# CIRCLE.net
KiCad netlist of a schematic drawn in EAGLE
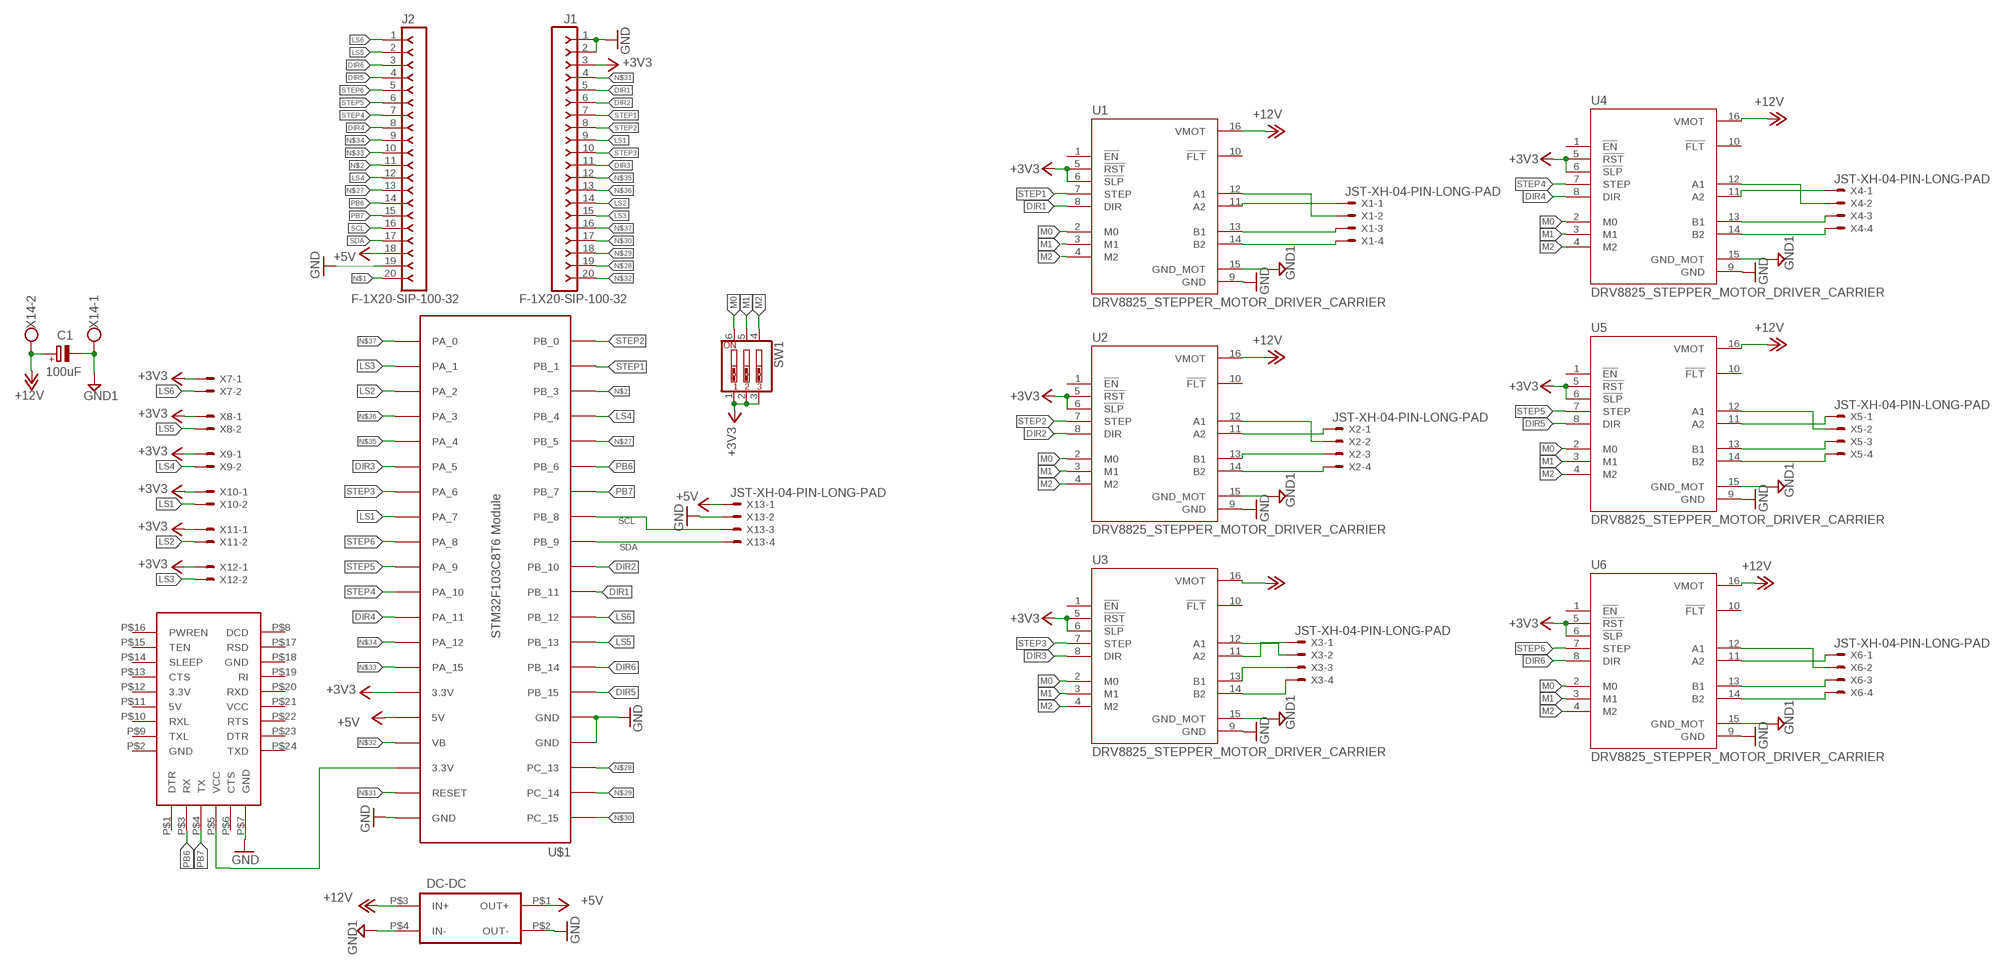
[diagram p0: schematic, sheet 1]

(export (version "E")
  (design (tool "Eeschema 10.0.6"))
  (components
    (comp (ref "C1")
      (value "100uF")
      (footprint "eagle-import:E3,5-8")
      (libsource (lib "eagle-import") (part "CPOL-EUE3.5-8"))
    )
    (comp (ref "J1")
      (value "F-1X20-SIP-100-32")
      (footprint "eagle-import:SIP-100-20-32")
      (libsource (lib "eagle-import") (part "F-1X20-SIP-100-32"))
    )
    (comp (ref "J2")
      (value "F-1X20-SIP-100-32")
      (footprint "eagle-import:SIP-100-20-32")
      (libsource (lib "eagle-import") (part "F-1X20-SIP-100-32"))
    )
    (comp (ref "SW1")
      (value "SW_DIP-3")
      (footprint "eagle-import:EDG-03")
      (libsource (lib "eagle-import") (part "SW_DIP-3"))
    )
    (comp (ref "U$1")
      (value "STM32F103C8T6-MODULE")
      (footprint "eagle-import:STM32F103C8T6-MODULE")
      (libsource (lib "eagle-import") (part "STM32F103C8T6-MODULE"))
    )
    (comp (ref "U$2")
      (value "DC-DC_CONV")
      (footprint "eagle-import:DC-DC_CONV")
      (libsource (lib "eagle-import") (part "DC-DC_CONV"))
    )
    (comp (ref "U$3")
      (value "FT232RL_FTDI")
      (footprint "eagle-import:FT232RL_FTDI")
      (libsource (lib "eagle-import") (part "FT232RL_FTDI"))
    )
    (comp (ref "U1")
      (value "DRV8825_STEPPER_MOTOR_DRIVER_CARRIER")
      (footprint "eagle-import:IC_DRV8825_STEPPER_MOTOR_DRIVER_CARRIER")
      (fields (field (name "MF") "Pololu") (field (name "MP") "DRV8825 STEPPER MOTOR DRIVER CARRIER"))
      (libsource (lib "eagle-import") (part "DRV8825_STEPPER_MOTOR_DRIVER_CARRIER"))
    )
    (comp (ref "U2")
      (value "DRV8825_STEPPER_MOTOR_DRIVER_CARRIER")
      (footprint "eagle-import:IC_DRV8825_STEPPER_MOTOR_DRIVER_CARRIER")
      (fields (field (name "MF") "Pololu") (field (name "MP") "DRV8825 STEPPER MOTOR DRIVER CARRIER"))
      (libsource (lib "eagle-import") (part "DRV8825_STEPPER_MOTOR_DRIVER_CARRIER"))
    )
    (comp (ref "U3")
      (value "DRV8825_STEPPER_MOTOR_DRIVER_CARRIER")
      (footprint "eagle-import:IC_DRV8825_STEPPER_MOTOR_DRIVER_CARRIER")
      (fields (field (name "MF") "Pololu") (field (name "MP") "DRV8825 STEPPER MOTOR DRIVER CARRIER"))
      (libsource (lib "eagle-import") (part "DRV8825_STEPPER_MOTOR_DRIVER_CARRIER"))
    )
    (comp (ref "U4")
      (value "DRV8825_STEPPER_MOTOR_DRIVER_CARRIER")
      (footprint "eagle-import:IC_DRV8825_STEPPER_MOTOR_DRIVER_CARRIER")
      (fields (field (name "MF") "Pololu") (field (name "MP") "DRV8825 STEPPER MOTOR DRIVER CARRIER"))
      (libsource (lib "eagle-import") (part "DRV8825_STEPPER_MOTOR_DRIVER_CARRIER"))
    )
    (comp (ref "U5")
      (value "DRV8825_STEPPER_MOTOR_DRIVER_CARRIER")
      (footprint "eagle-import:IC_DRV8825_STEPPER_MOTOR_DRIVER_CARRIER")
      (fields (field (name "MF") "Pololu") (field (name "MP") "DRV8825 STEPPER MOTOR DRIVER CARRIER"))
      (libsource (lib "eagle-import") (part "DRV8825_STEPPER_MOTOR_DRIVER_CARRIER"))
    )
    (comp (ref "U6")
      (value "DRV8825_STEPPER_MOTOR_DRIVER_CARRIER")
      (footprint "eagle-import:IC_DRV8825_STEPPER_MOTOR_DRIVER_CARRIER")
      (fields (field (name "MF") "Pololu") (field (name "MP") "DRV8825 STEPPER MOTOR DRIVER CARRIER"))
      (libsource (lib "eagle-import") (part "DRV8825_STEPPER_MOTOR_DRIVER_CARRIER"))
    )
    (comp (ref "X1")
      (value "JST-XH-04-PIN-LONG-PAD")
      (footprint "eagle-import:JST-XH-04-PACKAGE-LONG-PAD")
      (libsource (lib "eagle-import") (part "JST-XH-04-PIN-LONG-PAD"))
    )
    (comp (ref "X2")
      (value "JST-XH-04-PIN-LONG-PAD")
      (footprint "eagle-import:JST-XH-04-PACKAGE-LONG-PAD")
      (libsource (lib "eagle-import") (part "JST-XH-04-PIN-LONG-PAD"))
    )
    (comp (ref "X3")
      (value "JST-XH-04-PIN-LONG-PAD")
      (footprint "eagle-import:JST-XH-04-PACKAGE-LONG-PAD")
      (libsource (lib "eagle-import") (part "JST-XH-04-PIN-LONG-PAD"))
    )
    (comp (ref "X4")
      (value "JST-XH-04-PIN-LONG-PAD")
      (footprint "eagle-import:JST-XH-04-PACKAGE-LONG-PAD")
      (libsource (lib "eagle-import") (part "JST-XH-04-PIN-LONG-PAD"))
    )
    (comp (ref "X5")
      (value "JST-XH-04-PIN-LONG-PAD")
      (footprint "eagle-import:JST-XH-04-PACKAGE-LONG-PAD")
      (libsource (lib "eagle-import") (part "JST-XH-04-PIN-LONG-PAD"))
    )
    (comp (ref "X6")
      (value "JST-XH-04-PIN-LONG-PAD")
      (footprint "eagle-import:JST-XH-04-PACKAGE-LONG-PAD")
      (libsource (lib "eagle-import") (part "JST-XH-04-PIN-LONG-PAD"))
    )
    (comp (ref "X7")
      (value "JST-XH-02-PIN-LONG-PAD")
      (footprint "eagle-import:JST-XH-02-PACKAGE-LONG-PAD")
      (libsource (lib "eagle-import") (part "JST-XH-02-PIN-LONG-PAD"))
    )
    (comp (ref "X8")
      (value "JST-XH-02-PIN-LONG-PAD")
      (footprint "eagle-import:JST-XH-02-PACKAGE-LONG-PAD")
      (libsource (lib "eagle-import") (part "JST-XH-02-PIN-LONG-PAD"))
    )
    (comp (ref "X9")
      (value "JST-XH-02-PIN-LONG-PAD")
      (footprint "eagle-import:JST-XH-02-PACKAGE-LONG-PAD")
      (libsource (lib "eagle-import") (part "JST-XH-02-PIN-LONG-PAD"))
    )
    (comp (ref "X10")
      (value "JST-XH-02-PIN-LONG-PAD")
      (footprint "eagle-import:JST-XH-02-PACKAGE-LONG-PAD")
      (libsource (lib "eagle-import") (part "JST-XH-02-PIN-LONG-PAD"))
    )
    (comp (ref "X11")
      (value "JST-XH-02-PIN-LONG-PAD")
      (footprint "eagle-import:JST-XH-02-PACKAGE-LONG-PAD")
      (libsource (lib "eagle-import") (part "JST-XH-02-PIN-LONG-PAD"))
    )
    (comp (ref "X12")
      (value "JST-XH-02-PIN-LONG-PAD")
      (footprint "eagle-import:JST-XH-02-PACKAGE-LONG-PAD")
      (libsource (lib "eagle-import") (part "JST-XH-02-PIN-LONG-PAD"))
    )
    (comp (ref "X13")
      (value "JST-XH-04-PIN-LONG-PAD")
      (footprint "eagle-import:JST-XH-04-PACKAGE-LONG-PAD")
      (libsource (lib "eagle-import") (part "JST-XH-04-PIN-LONG-PAD"))
    )
    (comp (ref "X14")
      (value "W237-102")
      (footprint "eagle-import:W237-102")
      (fields (field (name "MPN") "237-102"))
      (libsource (lib "eagle-import") (part "W237-102"))
    )
  )
  (nets
    (net (code "1") (name "+3V3") (class "Default")
      (node (ref "J1") (pin "3") (pinfunction "3_3") (pintype "passive"))
      (node (ref "SW1") (pin "1") (pinfunction "1_1") (pintype "passive"))
      (node (ref "SW1") (pin "2") (pinfunction "2_2") (pintype "passive"))
      (node (ref "SW1") (pin "3") (pinfunction "3_3") (pintype "passive"))
      (node (ref "U$1") (pin "3.3V@2") (pinfunction "3.3V_3.3V@2") (pintype "bidirectional"))
      (node (ref "U1") (pin "5") (pinfunction "~{RST}_5") (pintype "input"))
      (node (ref "U1") (pin "6") (pinfunction "~{SLP}_6") (pintype "input"))
      (node (ref "U2") (pin "5") (pinfunction "~{RST}_5") (pintype "input"))
      (node (ref "U2") (pin "6") (pinfunction "~{SLP}_6") (pintype "input"))
      (node (ref "U3") (pin "5") (pinfunction "~{RST}_5") (pintype "input"))
      (node (ref "U3") (pin "6") (pinfunction "~{SLP}_6") (pintype "input"))
      (node (ref "U4") (pin "5") (pinfunction "~{RST}_5") (pintype "input"))
      (node (ref "U4") (pin "6") (pinfunction "~{SLP}_6") (pintype "input"))
      (node (ref "U5") (pin "5") (pinfunction "~{RST}_5") (pintype "input"))
      (node (ref "U5") (pin "6") (pinfunction "~{SLP}_6") (pintype "input"))
      (node (ref "U6") (pin "5") (pinfunction "~{RST}_5") (pintype "input"))
      (node (ref "U6") (pin "6") (pinfunction "~{SLP}_6") (pintype "input"))
      (node (ref "X10") (pin "1") (pinfunction "S_1") (pintype "passive"))
      (node (ref "X11") (pin "1") (pinfunction "S_1") (pintype "passive"))
      (node (ref "X12") (pin "1") (pinfunction "S_1") (pintype "passive"))
      (node (ref "X7") (pin "1") (pinfunction "S_1") (pintype "passive"))
      (node (ref "X8") (pin "1") (pinfunction "S_1") (pintype "passive"))
      (node (ref "X9") (pin "1") (pinfunction "S_1") (pintype "passive"))
    )
    (net (code "2") (name "+5V") (class "Default")
      (node (ref "J2") (pin "18") (pinfunction "18_18") (pintype "passive"))
      (node (ref "U$1") (pin "5V") (pinfunction "5V_5V") (pintype "bidirectional"))
      (node (ref "U$2") (pin "P$1") (pinfunction "OUT+_P$1") (pintype "bidirectional"))
      (node (ref "X13") (pin "1") (pinfunction "S_1") (pintype "passive"))
    )
    (net (code "3") (name "+12V") (class "Default")
      (node (ref "C1") (pin "+") (pinfunction "+_+") (pintype "passive"))
      (node (ref "U$2") (pin "P$3") (pinfunction "IN+_P$3") (pintype "bidirectional"))
      (node (ref "U1") (pin "16") (pinfunction "VMOT_16") (pintype "power_in"))
      (node (ref "U2") (pin "16") (pinfunction "VMOT_16") (pintype "power_in"))
      (node (ref "U3") (pin "16") (pinfunction "VMOT_16") (pintype "power_in"))
      (node (ref "U4") (pin "16") (pinfunction "VMOT_16") (pintype "power_in"))
      (node (ref "U5") (pin "16") (pinfunction "VMOT_16") (pintype "power_in"))
      (node (ref "U6") (pin "16") (pinfunction "VMOT_16") (pintype "power_in"))
      (node (ref "X14") (pin "2") (pinfunction "KL_2") (pintype "passive"))
    )
    (net (code "4") (name "DIR1") (class "Default")
      (node (ref "J1") (pin "5") (pinfunction "5_5") (pintype "passive"))
      (node (ref "U$1") (pin "PB_11") (pinfunction "PB_11_PB_11") (pintype "bidirectional"))
      (node (ref "U1") (pin "8") (pinfunction "DIR_8") (pintype "input"))
    )
    (net (code "5") (name "DIR2") (class "Default")
      (node (ref "J1") (pin "6") (pinfunction "6_6") (pintype "passive"))
      (node (ref "U$1") (pin "PB_10") (pinfunction "PB_10_PB_10") (pintype "bidirectional"))
      (node (ref "U2") (pin "8") (pinfunction "DIR_8") (pintype "input"))
    )
    (net (code "6") (name "DIR3") (class "Default")
      (node (ref "J1") (pin "11") (pinfunction "11_11") (pintype "passive"))
      (node (ref "U$1") (pin "PA_5") (pinfunction "PA_5_PA_5") (pintype "bidirectional"))
      (node (ref "U3") (pin "8") (pinfunction "DIR_8") (pintype "input"))
    )
    (net (code "7") (name "DIR4") (class "Default")
      (node (ref "J2") (pin "8") (pinfunction "8_8") (pintype "passive"))
      (node (ref "U$1") (pin "PA_11") (pinfunction "PA_11_PA_11") (pintype "bidirectional"))
      (node (ref "U4") (pin "8") (pinfunction "DIR_8") (pintype "input"))
    )
    (net (code "8") (name "DIR5") (class "Default")
      (node (ref "J2") (pin "4") (pinfunction "4_4") (pintype "passive"))
      (node (ref "U$1") (pin "PB_15") (pinfunction "PB_15_PB_15") (pintype "bidirectional"))
      (node (ref "U5") (pin "8") (pinfunction "DIR_8") (pintype "input"))
    )
    (net (code "9") (name "DIR6") (class "Default")
      (node (ref "J2") (pin "3") (pinfunction "3_3") (pintype "passive"))
      (node (ref "U$1") (pin "PB_14") (pinfunction "PB_14_PB_14") (pintype "bidirectional"))
      (node (ref "U6") (pin "8") (pinfunction "DIR_8") (pintype "input"))
    )
    (net (code "10") (name "GND") (class "Default")
      (node (ref "J1") (pin "1") (pinfunction "1_1") (pintype "passive"))
      (node (ref "J1") (pin "2") (pinfunction "2_2") (pintype "passive"))
      (node (ref "J2") (pin "19") (pinfunction "19_19") (pintype "passive"))
      (node (ref "U$1") (pin "GND@1") (pinfunction "GND_GND@1") (pintype "bidirectional"))
      (node (ref "U$1") (pin "GND@2") (pinfunction "GND_GND@2") (pintype "bidirectional"))
      (node (ref "U$1") (pin "GND@3") (pinfunction "GND_GND@3") (pintype "bidirectional"))
      (node (ref "U$2") (pin "P$2") (pinfunction "OUT-_P$2") (pintype "bidirectional"))
      (node (ref "U$3") (pin "P$7") (pinfunction "GND_P$7") (pintype "bidirectional"))
      (node (ref "U1") (pin "9") (pinfunction "GND_9") (pintype "power_in"))
      (node (ref "U2") (pin "9") (pinfunction "GND_9") (pintype "power_in"))
      (node (ref "U3") (pin "9") (pinfunction "GND_9") (pintype "power_in"))
      (node (ref "U4") (pin "9") (pinfunction "GND_9") (pintype "power_in"))
      (node (ref "U5") (pin "9") (pinfunction "GND_9") (pintype "power_in"))
      (node (ref "U6") (pin "9") (pinfunction "GND_9") (pintype "power_in"))
      (node (ref "X13") (pin "2") (pinfunction "S_2") (pintype "passive"))
    )
    (net (code "11") (name "GND1") (class "Default")
      (node (ref "C1") (pin "-") (pinfunction "-_-") (pintype "passive"))
      (node (ref "U$2") (pin "P$4") (pinfunction "IN-_P$4") (pintype "bidirectional"))
      (node (ref "U1") (pin "15") (pinfunction "GND_MOT_15") (pintype "power_in"))
      (node (ref "U2") (pin "15") (pinfunction "GND_MOT_15") (pintype "power_in"))
      (node (ref "U3") (pin "15") (pinfunction "GND_MOT_15") (pintype "power_in"))
      (node (ref "U4") (pin "15") (pinfunction "GND_MOT_15") (pintype "power_in"))
      (node (ref "U5") (pin "15") (pinfunction "GND_MOT_15") (pintype "power_in"))
      (node (ref "U6") (pin "15") (pinfunction "GND_MOT_15") (pintype "power_in"))
      (node (ref "X14") (pin "1") (pinfunction "KL_1") (pintype "passive"))
    )
    (net (code "12") (name "LS1") (class "Default")
      (node (ref "J1") (pin "9") (pinfunction "9_9") (pintype "passive"))
      (node (ref "U$1") (pin "PA_7") (pinfunction "PA_7_PA_7") (pintype "bidirectional"))
      (node (ref "X10") (pin "2") (pinfunction "S_2") (pintype "passive"))
    )
    (net (code "13") (name "LS2") (class "Default")
      (node (ref "J1") (pin "14") (pinfunction "14_14") (pintype "passive"))
      (node (ref "U$1") (pin "PA_2") (pinfunction "PA_2_PA_2") (pintype "bidirectional"))
      (node (ref "X11") (pin "2") (pinfunction "S_2") (pintype "passive"))
    )
    (net (code "14") (name "LS3") (class "Default")
      (node (ref "J1") (pin "15") (pinfunction "15_15") (pintype "passive"))
      (node (ref "U$1") (pin "PA_1") (pinfunction "PA_1_PA_1") (pintype "bidirectional"))
      (node (ref "X12") (pin "2") (pinfunction "S_2") (pintype "passive"))
    )
    (net (code "15") (name "LS4") (class "Default")
      (node (ref "J2") (pin "12") (pinfunction "12_12") (pintype "passive"))
      (node (ref "U$1") (pin "PB_4") (pinfunction "PB_4_PB_4") (pintype "bidirectional"))
      (node (ref "X9") (pin "2") (pinfunction "S_2") (pintype "passive"))
    )
    (net (code "16") (name "LS5") (class "Default")
      (node (ref "J2") (pin "2") (pinfunction "2_2") (pintype "passive"))
      (node (ref "U$1") (pin "PB_13") (pinfunction "PB_13_PB_13") (pintype "bidirectional"))
      (node (ref "X8") (pin "2") (pinfunction "S_2") (pintype "passive"))
    )
    (net (code "17") (name "LS6") (class "Default")
      (node (ref "J2") (pin "1") (pinfunction "1_1") (pintype "passive"))
      (node (ref "U$1") (pin "PB_12") (pinfunction "PB_12_PB_12") (pintype "bidirectional"))
      (node (ref "X7") (pin "2") (pinfunction "S_2") (pintype "passive"))
    )
    (net (code "18") (name "M0") (class "Default")
      (node (ref "SW1") (pin "6") (pinfunction "6_6") (pintype "passive"))
      (node (ref "U1") (pin "2") (pinfunction "M0_2") (pintype "input"))
      (node (ref "U2") (pin "2") (pinfunction "M0_2") (pintype "input"))
      (node (ref "U3") (pin "2") (pinfunction "M0_2") (pintype "input"))
      (node (ref "U4") (pin "2") (pinfunction "M0_2") (pintype "input"))
      (node (ref "U5") (pin "2") (pinfunction "M0_2") (pintype "input"))
      (node (ref "U6") (pin "2") (pinfunction "M0_2") (pintype "input"))
    )
    (net (code "19") (name "M1") (class "Default")
      (node (ref "SW1") (pin "5") (pinfunction "5_5") (pintype "passive"))
      (node (ref "U1") (pin "3") (pinfunction "M1_3") (pintype "input"))
      (node (ref "U2") (pin "3") (pinfunction "M1_3") (pintype "input"))
      (node (ref "U3") (pin "3") (pinfunction "M1_3") (pintype "input"))
      (node (ref "U4") (pin "3") (pinfunction "M1_3") (pintype "input"))
      (node (ref "U5") (pin "3") (pinfunction "M1_3") (pintype "input"))
      (node (ref "U6") (pin "3") (pinfunction "M1_3") (pintype "input"))
    )
    (net (code "20") (name "M2") (class "Default")
      (node (ref "SW1") (pin "4") (pinfunction "4_4") (pintype "passive"))
      (node (ref "U1") (pin "4") (pinfunction "M2_4") (pintype "input"))
      (node (ref "U2") (pin "4") (pinfunction "M2_4") (pintype "input"))
      (node (ref "U3") (pin "4") (pinfunction "M2_4") (pintype "input"))
      (node (ref "U4") (pin "4") (pinfunction "M2_4") (pintype "input"))
      (node (ref "U5") (pin "4") (pinfunction "M2_4") (pintype "input"))
      (node (ref "U6") (pin "4") (pinfunction "M2_4") (pintype "input"))
    )
    (net (code "21") (name "N$1") (class "Default")
      (node (ref "J2") (pin "20") (pinfunction "20_20") (pintype "passive"))
      (node (ref "U$1") (pin "3.3V@1") (pinfunction "3.3V_3.3V@1") (pintype "bidirectional"))
      (node (ref "U$3") (pin "P$5") (pinfunction "VCC_P$5") (pintype "bidirectional"))
    )
    (net (code "22") (name "N$2") (class "Default")
      (node (ref "J2") (pin "11") (pinfunction "11_11") (pintype "passive"))
      (node (ref "U$1") (pin "PB_3") (pinfunction "PB_3_PB_3") (pintype "bidirectional"))
    )
    (net (code "23") (name "N$27") (class "Default")
      (node (ref "J2") (pin "13") (pinfunction "13_13") (pintype "passive"))
      (node (ref "U$1") (pin "PB_5") (pinfunction "PB_5_PB_5") (pintype "bidirectional"))
    )
    (net (code "24") (name "N$28") (class "Default")
      (node (ref "J1") (pin "19") (pinfunction "19_19") (pintype "passive"))
      (node (ref "U$1") (pin "PC_13") (pinfunction "PC_13_PC_13") (pintype "bidirectional"))
    )
    (net (code "25") (name "N$29") (class "Default")
      (node (ref "J1") (pin "18") (pinfunction "18_18") (pintype "passive"))
      (node (ref "U$1") (pin "PC_14") (pinfunction "PC_14_PC_14") (pintype "bidirectional"))
    )
    (net (code "26") (name "N$30") (class "Default")
      (node (ref "J1") (pin "17") (pinfunction "17_17") (pintype "passive"))
      (node (ref "U$1") (pin "PC_15") (pinfunction "PC_15_PC_15") (pintype "bidirectional"))
    )
    (net (code "27") (name "N$31") (class "Default")
      (node (ref "J1") (pin "4") (pinfunction "4_4") (pintype "passive"))
      (node (ref "U$1") (pin "RESET") (pinfunction "RESET_RESET") (pintype "bidirectional"))
    )
    (net (code "28") (name "N$32") (class "Default")
      (node (ref "J1") (pin "20") (pinfunction "20_20") (pintype "passive"))
      (node (ref "U$1") (pin "VB") (pinfunction "VB_VB") (pintype "bidirectional"))
    )
    (net (code "29") (name "N$33") (class "Default")
      (node (ref "J2") (pin "10") (pinfunction "10_10") (pintype "passive"))
      (node (ref "U$1") (pin "PA_15") (pinfunction "PA_15_PA_15") (pintype "bidirectional"))
    )
    (net (code "30") (name "N$34") (class "Default")
      (node (ref "J2") (pin "9") (pinfunction "9_9") (pintype "passive"))
      (node (ref "U$1") (pin "PA_12") (pinfunction "PA_12_PA_12") (pintype "bidirectional"))
    )
    (net (code "31") (name "N$35") (class "Default")
      (node (ref "J1") (pin "12") (pinfunction "12_12") (pintype "passive"))
      (node (ref "U$1") (pin "PA_4") (pinfunction "PA_4_PA_4") (pintype "bidirectional"))
    )
    (net (code "32") (name "N$36") (class "Default")
      (node (ref "J1") (pin "13") (pinfunction "13_13") (pintype "passive"))
      (node (ref "U$1") (pin "PA_3") (pinfunction "PA_3_PA_3") (pintype "bidirectional"))
    )
    (net (code "33") (name "N$37") (class "Default")
      (node (ref "J1") (pin "16") (pinfunction "16_16") (pintype "passive"))
      (node (ref "U$1") (pin "PA_0") (pinfunction "PA_0_PA_0") (pintype "bidirectional"))
    )
    (net (code "34") (name "Net-(U1-A1)") (class "Default")
      (node (ref "U1") (pin "12") (pinfunction "A1_12") (pintype "output"))
      (node (ref "X1") (pin "2") (pinfunction "S_2") (pintype "passive"))
    )
    (net (code "35") (name "Net-(U1-A2)") (class "Default")
      (node (ref "U1") (pin "11") (pinfunction "A2_11") (pintype "output"))
      (node (ref "X1") (pin "1") (pinfunction "S_1") (pintype "passive"))
    )
    (net (code "36") (name "Net-(U1-B1)") (class "Default")
      (node (ref "U1") (pin "13") (pinfunction "B1_13") (pintype "output"))
      (node (ref "X1") (pin "3") (pinfunction "S_3") (pintype "passive"))
    )
    (net (code "37") (name "Net-(U1-B2)") (class "Default")
      (node (ref "U1") (pin "14") (pinfunction "B2_14") (pintype "output"))
      (node (ref "X1") (pin "4") (pinfunction "S_4") (pintype "passive"))
    )
    (net (code "38") (name "Net-(U2-A1)") (class "Default")
      (node (ref "U2") (pin "12") (pinfunction "A1_12") (pintype "output"))
      (node (ref "X2") (pin "2") (pinfunction "S_2") (pintype "passive"))
    )
    (net (code "39") (name "Net-(U2-A2)") (class "Default")
      (node (ref "U2") (pin "11") (pinfunction "A2_11") (pintype "output"))
      (node (ref "X2") (pin "1") (pinfunction "S_1") (pintype "passive"))
    )
    (net (code "40") (name "Net-(U2-B1)") (class "Default")
      (node (ref "U2") (pin "13") (pinfunction "B1_13") (pintype "output"))
      (node (ref "X2") (pin "3") (pinfunction "S_3") (pintype "passive"))
    )
    (net (code "41") (name "Net-(U2-B2)") (class "Default")
      (node (ref "U2") (pin "14") (pinfunction "B2_14") (pintype "output"))
      (node (ref "X2") (pin "4") (pinfunction "S_4") (pintype "passive"))
    )
    (net (code "42") (name "Net-(U3-A1)") (class "Default")
      (node (ref "U3") (pin "12") (pinfunction "A1_12") (pintype "output"))
      (node (ref "X3") (pin "2") (pinfunction "S_2") (pintype "passive"))
    )
    (net (code "43") (name "Net-(U3-A2)") (class "Default")
      (node (ref "U3") (pin "11") (pinfunction "A2_11") (pintype "output"))
      (node (ref "X3") (pin "1") (pinfunction "S_1") (pintype "passive"))
    )
    (net (code "44") (name "Net-(U3-B1)") (class "Default")
      (node (ref "U3") (pin "13") (pinfunction "B1_13") (pintype "output"))
      (node (ref "X3") (pin "3") (pinfunction "S_3") (pintype "passive"))
    )
    (net (code "45") (name "Net-(U3-B2)") (class "Default")
      (node (ref "U3") (pin "14") (pinfunction "B2_14") (pintype "output"))
      (node (ref "X3") (pin "4") (pinfunction "S_4") (pintype "passive"))
    )
    (net (code "46") (name "Net-(U4-A1)") (class "Default")
      (node (ref "U4") (pin "12") (pinfunction "A1_12") (pintype "output"))
      (node (ref "X4") (pin "2") (pinfunction "S_2") (pintype "passive"))
    )
    (net (code "47") (name "Net-(U4-A2)") (class "Default")
      (node (ref "U4") (pin "11") (pinfunction "A2_11") (pintype "output"))
      (node (ref "X4") (pin "1") (pinfunction "S_1") (pintype "passive"))
    )
    (net (code "48") (name "Net-(U4-B1)") (class "Default")
      (node (ref "U4") (pin "13") (pinfunction "B1_13") (pintype "output"))
      (node (ref "X4") (pin "3") (pinfunction "S_3") (pintype "passive"))
    )
    (net (code "49") (name "Net-(U4-B2)") (class "Default")
      (node (ref "U4") (pin "14") (pinfunction "B2_14") (pintype "output"))
      (node (ref "X4") (pin "4") (pinfunction "S_4") (pintype "passive"))
    )
    (net (code "50") (name "Net-(U5-A1)") (class "Default")
      (node (ref "U5") (pin "12") (pinfunction "A1_12") (pintype "output"))
      (node (ref "X5") (pin "2") (pinfunction "S_2") (pintype "passive"))
    )
    (net (code "51") (name "Net-(U5-A2)") (class "Default")
      (node (ref "U5") (pin "11") (pinfunction "A2_11") (pintype "output"))
      (node (ref "X5") (pin "1") (pinfunction "S_1") (pintype "passive"))
    )
    (net (code "52") (name "Net-(U5-B1)") (class "Default")
      (node (ref "U5") (pin "13") (pinfunction "B1_13") (pintype "output"))
      (node (ref "X5") (pin "3") (pinfunction "S_3") (pintype "passive"))
    )
    (net (code "53") (name "Net-(U5-B2)") (class "Default")
      (node (ref "U5") (pin "14") (pinfunction "B2_14") (pintype "output"))
      (node (ref "X5") (pin "4") (pinfunction "S_4") (pintype "passive"))
    )
    (net (code "54") (name "Net-(U6-A1)") (class "Default")
      (node (ref "U6") (pin "12") (pinfunction "A1_12") (pintype "output"))
      (node (ref "X6") (pin "2") (pinfunction "S_2") (pintype "passive"))
    )
    (net (code "55") (name "Net-(U6-A2)") (class "Default")
      (node (ref "U6") (pin "11") (pinfunction "A2_11") (pintype "output"))
      (node (ref "X6") (pin "1") (pinfunction "S_1") (pintype "passive"))
    )
    (net (code "56") (name "Net-(U6-B1)") (class "Default")
      (node (ref "U6") (pin "13") (pinfunction "B1_13") (pintype "output"))
      (node (ref "X6") (pin "3") (pinfunction "S_3") (pintype "passive"))
    )
    (net (code "57") (name "Net-(U6-B2)") (class "Default")
      (node (ref "U6") (pin "14") (pinfunction "B2_14") (pintype "output"))
      (node (ref "X6") (pin "4") (pinfunction "S_4") (pintype "passive"))
    )
    (net (code "58") (name "PB6") (class "Default")
      (node (ref "J2") (pin "14") (pinfunction "14_14") (pintype "passive"))
      (node (ref "U$1") (pin "PB_6") (pinfunction "PB_6_PB_6") (pintype "bidirectional"))
      (node (ref "U$3") (pin "P$3") (pinfunction "RX_P$3") (pintype "bidirectional"))
    )
    (net (code "59") (name "PB7") (class "Default")
      (node (ref "J2") (pin "15") (pinfunction "15_15") (pintype "passive"))
      (node (ref "U$1") (pin "PB_7") (pinfunction "PB_7_PB_7") (pintype "bidirectional"))
      (node (ref "U$3") (pin "P$4") (pinfunction "TX_P$4") (pintype "bidirectional"))
    )
    (net (code "60") (name "SCL") (class "Default")
      (node (ref "J2") (pin "16") (pinfunction "16_16") (pintype "passive"))
      (node (ref "U$1") (pin "PB_8") (pinfunction "PB_8_PB_8") (pintype "bidirectional"))
      (node (ref "X13") (pin "3") (pinfunction "S_3") (pintype "passive"))
    )
    (net (code "61") (name "SDA") (class "Default")
      (node (ref "J2") (pin "17") (pinfunction "17_17") (pintype "passive"))
      (node (ref "U$1") (pin "PB_9") (pinfunction "PB_9_PB_9") (pintype "bidirectional"))
      (node (ref "X13") (pin "4") (pinfunction "S_4") (pintype "passive"))
    )
    (net (code "62") (name "STEP1") (class "Default")
      (node (ref "J1") (pin "7") (pinfunction "7_7") (pintype "passive"))
      (node (ref "U$1") (pin "PB_1") (pinfunction "PB_1_PB_1") (pintype "bidirectional"))
      (node (ref "U1") (pin "7") (pinfunction "STEP_7") (pintype "input"))
    )
    (net (code "63") (name "STEP2") (class "Default")
      (node (ref "J1") (pin "8") (pinfunction "8_8") (pintype "passive"))
      (node (ref "U$1") (pin "PB_0") (pinfunction "PB_0_PB_0") (pintype "bidirectional"))
      (node (ref "U2") (pin "7") (pinfunction "STEP_7") (pintype "input"))
    )
    (net (code "64") (name "STEP3") (class "Default")
      (node (ref "J1") (pin "10") (pinfunction "10_10") (pintype "passive"))
      (node (ref "U$1") (pin "PA_6") (pinfunction "PA_6_PA_6") (pintype "bidirectional"))
      (node (ref "U3") (pin "7") (pinfunction "STEP_7") (pintype "input"))
    )
    (net (code "65") (name "STEP4") (class "Default")
      (node (ref "J2") (pin "7") (pinfunction "7_7") (pintype "passive"))
      (node (ref "U$1") (pin "PA_10") (pinfunction "PA_10_PA_10") (pintype "bidirectional"))
      (node (ref "U4") (pin "7") (pinfunction "STEP_7") (pintype "input"))
    )
    (net (code "66") (name "STEP5") (class "Default")
      (node (ref "J2") (pin "6") (pinfunction "6_6") (pintype "passive"))
      (node (ref "U$1") (pin "PA_9") (pinfunction "PA_9_PA_9") (pintype "bidirectional"))
      (node (ref "U5") (pin "7") (pinfunction "STEP_7") (pintype "input"))
    )
    (net (code "67") (name "STEP6") (class "Default")
      (node (ref "J2") (pin "5") (pinfunction "5_5") (pintype "passive"))
      (node (ref "U$1") (pin "PA_8") (pinfunction "PA_8_PA_8") (pintype "bidirectional"))
      (node (ref "U6") (pin "7") (pinfunction "STEP_7") (pintype "input"))
    )
    (net (code "68") (name "unconnected-(U$3-3.3V-PadP$12)") (class "Default")
      (node (ref "U$3") (pin "P$12") (pinfunction "3.3V_P$12") (pintype "bidirectional"))
    )
    (net (code "69") (name "unconnected-(U$3-5V-PadP$11)") (class "Default")
      (node (ref "U$3") (pin "P$11") (pinfunction "5V_P$11") (pintype "bidirectional"))
    )
    (net (code "70") (name "unconnected-(U$3-CTS-PadP$6)") (class "Default")
      (node (ref "U$3") (pin "P$6") (pinfunction "CTS_P$6") (pintype "bidirectional"))
    )
    (net (code "71") (name "unconnected-(U$3-CTS-PadP$13)") (class "Default")
      (node (ref "U$3") (pin "P$13") (pinfunction "CTS_P$13") (pintype "bidirectional"))
    )
    (net (code "72") (name "unconnected-(U$3-DCD-PadP$8)") (class "Default")
      (node (ref "U$3") (pin "P$8") (pinfunction "DCD_P$8") (pintype "bidirectional"))
    )
    (net (code "73") (name "unconnected-(U$3-DTR-PadP$1)") (class "Default")
      (node (ref "U$3") (pin "P$1") (pinfunction "DTR_P$1") (pintype "bidirectional"))
    )
    (net (code "74") (name "unconnected-(U$3-DTR-PadP$23)") (class "Default")
      (node (ref "U$3") (pin "P$23") (pinfunction "DTR_P$23") (pintype "bidirectional"))
    )
    (net (code "75") (name "unconnected-(U$3-GND-PadP$2)") (class "Default")
      (node (ref "U$3") (pin "P$2") (pinfunction "GND_P$2") (pintype "bidirectional"))
    )
    (net (code "76") (name "unconnected-(U$3-GND-PadP$18)") (class "Default")
      (node (ref "U$3") (pin "P$18") (pinfunction "GND_P$18") (pintype "bidirectional"))
    )
    (net (code "77") (name "unconnected-(U$3-PWREN-PadP$16)") (class "Default")
      (node (ref "U$3") (pin "P$16") (pinfunction "PWREN_P$16") (pintype "bidirectional"))
    )
    (net (code "78") (name "unconnected-(U$3-RI-PadP$19)") (class "Default")
      (node (ref "U$3") (pin "P$19") (pinfunction "RI_P$19") (pintype "bidirectional"))
    )
    (net (code "79") (name "unconnected-(U$3-RSD-PadP$17)") (class "Default")
      (node (ref "U$3") (pin "P$17") (pinfunction "RSD_P$17") (pintype "bidirectional"))
    )
    (net (code "80") (name "unconnected-(U$3-RTS-PadP$22)") (class "Default")
      (node (ref "U$3") (pin "P$22") (pinfunction "RTS_P$22") (pintype "bidirectional"))
    )
    (net (code "81") (name "unconnected-(U$3-RXD-PadP$20)") (class "Default")
      (node (ref "U$3") (pin "P$20") (pinfunction "RXD_P$20") (pintype "bidirectional"))
    )
    (net (code "82") (name "unconnected-(U$3-RXL-PadP$10)") (class "Default")
      (node (ref "U$3") (pin "P$10") (pinfunction "RXL_P$10") (pintype "bidirectional"))
    )
    (net (code "83") (name "unconnected-(U$3-SLEEP-PadP$14)") (class "Default")
      (node (ref "U$3") (pin "P$14") (pinfunction "SLEEP_P$14") (pintype "bidirectional"))
    )
    (net (code "84") (name "unconnected-(U$3-TEN-PadP$15)") (class "Default")
      (node (ref "U$3") (pin "P$15") (pinfunction "TEN_P$15") (pintype "bidirectional"))
    )
    (net (code "85") (name "unconnected-(U$3-TXD-PadP$24)") (class "Default")
      (node (ref "U$3") (pin "P$24") (pinfunction "TXD_P$24") (pintype "bidirectional"))
    )
    (net (code "86") (name "unconnected-(U$3-TXL-PadP$9)") (class "Default")
      (node (ref "U$3") (pin "P$9") (pinfunction "TXL_P$9") (pintype "bidirectional"))
    )
    (net (code "87") (name "unconnected-(U$3-VCC-PadP$21)") (class "Default")
      (node (ref "U$3") (pin "P$21") (pinfunction "VCC_P$21") (pintype "bidirectional"))
    )
    (net (code "88") (name "unconnected-(U1-~{EN}-Pad1)") (class "Default")
      (node (ref "U1") (pin "1") (pinfunction "~{EN}_1") (pintype "input"))
    )
    (net (code "89") (name "unconnected-(U1-~{FLT}-Pad10)") (class "Default")
      (node (ref "U1") (pin "10") (pinfunction "~{FLT}_10") (pintype "output"))
    )
    (net (code "90") (name "unconnected-(U2-~{EN}-Pad1)") (class "Default")
      (node (ref "U2") (pin "1") (pinfunction "~{EN}_1") (pintype "input"))
    )
    (net (code "91") (name "unconnected-(U2-~{FLT}-Pad10)") (class "Default")
      (node (ref "U2") (pin "10") (pinfunction "~{FLT}_10") (pintype "output"))
    )
    (net (code "92") (name "unconnected-(U3-~{EN}-Pad1)") (class "Default")
      (node (ref "U3") (pin "1") (pinfunction "~{EN}_1") (pintype "input"))
    )
    (net (code "93") (name "unconnected-(U3-~{FLT}-Pad10)") (class "Default")
      (node (ref "U3") (pin "10") (pinfunction "~{FLT}_10") (pintype "output"))
    )
    (net (code "94") (name "unconnected-(U4-~{EN}-Pad1)") (class "Default")
      (node (ref "U4") (pin "1") (pinfunction "~{EN}_1") (pintype "input"))
    )
    (net (code "95") (name "unconnected-(U4-~{FLT}-Pad10)") (class "Default")
      (node (ref "U4") (pin "10") (pinfunction "~{FLT}_10") (pintype "output"))
    )
    (net (code "96") (name "unconnected-(U5-~{EN}-Pad1)") (class "Default")
      (node (ref "U5") (pin "1") (pinfunction "~{EN}_1") (pintype "input"))
    )
    (net (code "97") (name "unconnected-(U5-~{FLT}-Pad10)") (class "Default")
      (node (ref "U5") (pin "10") (pinfunction "~{FLT}_10") (pintype "output"))
    )
    (net (code "98") (name "unconnected-(U6-~{EN}-Pad1)") (class "Default")
      (node (ref "U6") (pin "1") (pinfunction "~{EN}_1") (pintype "input"))
    )
    (net (code "99") (name "unconnected-(U6-~{FLT}-Pad10)") (class "Default")
      (node (ref "U6") (pin "10") (pinfunction "~{FLT}_10") (pintype "output"))
    )
  )
)
